# 02_Mobile_Power.net
KiCad netlist of a schematic drawn in Altium Designer
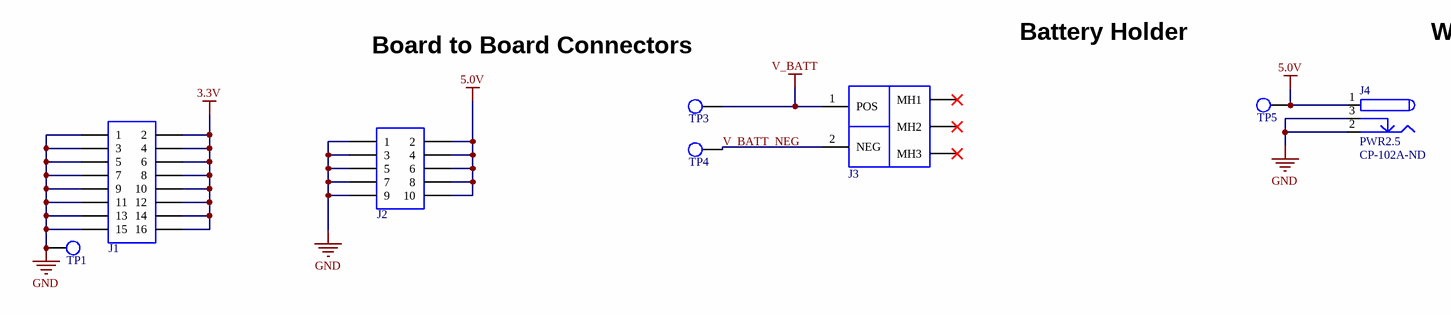
[diagram p0: 02 Mobile Power.SchDoc]

(export (version "E")
  (design (tool "Eeschema 10.0.6"))
  (components
    (comp (ref "J1")
      (value "CONN_HEADER_MALE_8x2")
      (footprint "SBH11-PBPC-D08-ST-BK")
      (description "CONN HEADER 2.54MM 16POS GOLD")
      (fields
        (field (name "MANUFACTURER") "Sullins Connector Solutions")
        (field (name "MANUFACTURER PART NUMBER") "SBH11-PBPC-D08-ST-BK")
      )
      (libsource (lib "ECE453_PWR") (part "CONN_HEADER_MALE_8x2"))
    )
    (comp (ref "J2")
      (value "CONN_HEADER_MALE_5x2")
      (footprint "SBH11-PBPC-D05-ST-BK")
      (description "CONN HEADER 2.54MM 10POS GOLD")
      (fields
        (field (name "MANUFACTURER PART NUMBER") "SBH11-PBPC-D05-ST-BK")
        (field (name "MANUFACTURER") "Sullins Connector Solutions")
      )
      (libsource (lib "ECE453_PWR") (part "CONN_HEADER_MALE_5x2"))
    )
    (comp (ref "J3")
      (value "CONN_BAT_18650")
      (footprint "1043")
      (description "HOLDER FOR 18650 BATTERY")
      (libsource (lib "Battery") (part "CONN_BAT_18650"))
    )
    (comp (ref "J4")
      (value "PWR2.5")
      (footprint "PJ-102")
      (description "Low Voltage Power Supply Connector")
      (fields
        (field (name "MANUFACTURER") "CUI")
        (field (name "MANUFACTURER PART NUMBER") "PJ-102A")
        (field (name "SUPPLIER PART NUMBER 1") "CP-102A-ND")
        (field (name "PUBLISHER") "Altium Limited")
      )
      (libsource (lib "ECE453_PWR") (part "PWR2.5"))
    )
    (comp (ref "TP1")
      (value "TP_1206")
      (footprint "TP-SMC-1206")
      (description "Test Point SMD 1206")
      (libsource (lib "ECE453_PWR") (part "TP_1206"))
    )
    (comp (ref "TP3")
      (value "TP_1206")
      (footprint "TP-SMC-1206")
      (description "Test Point SMD 1206")
      (libsource (lib "ECE453_PWR") (part "TP_1206"))
    )
    (comp (ref "TP4")
      (value "TP_1206")
      (footprint "TP-SMC-1206")
      (description "Test Point SMD 1206")
      (libsource (lib "ECE453_PWR") (part "TP_1206"))
    )
    (comp (ref "TP5")
      (value "TP_1206")
      (footprint "TP-SMC-1206")
      (description "Test Point SMD 1206")
      (libsource (lib "ECE453_PWR") (part "TP_1206"))
    )
  )
  (nets
    (net (code "1") (name "/V_BATT_NEG") (class "Default")
      (node (ref "J3") (pin "2") (pinfunction "NEG_2") (pintype "passive"))
      (node (ref "TP4") (pin "1") (pintype "passive"))
    )
    (net (code "2") (name "3.3V") (class "Default")
      (node (ref "J1") (pin "10") (pinfunction "10_10") (pintype "passive"))
      (node (ref "J1") (pin "12") (pinfunction "12_12") (pintype "passive"))
      (node (ref "J1") (pin "14") (pinfunction "14_14") (pintype "passive"))
      (node (ref "J1") (pin "16") (pinfunction "16_16") (pintype "passive"))
      (node (ref "J1") (pin "2") (pinfunction "2_2") (pintype "passive"))
      (node (ref "J1") (pin "4") (pinfunction "4_4") (pintype "passive"))
      (node (ref "J1") (pin "6") (pinfunction "6_6") (pintype "passive"))
      (node (ref "J1") (pin "8") (pinfunction "8_8") (pintype "passive"))
    )
    (net (code "3") (name "5.0V") (class "Default")
      (node (ref "J2") (pin "10") (pinfunction "10_10") (pintype "passive"))
      (node (ref "J2") (pin "2") (pinfunction "2_2") (pintype "passive"))
      (node (ref "J2") (pin "4") (pinfunction "4_4") (pintype "passive"))
      (node (ref "J2") (pin "6") (pinfunction "6_6") (pintype "passive"))
      (node (ref "J2") (pin "8") (pinfunction "8_8") (pintype "passive"))
      (node (ref "J4") (pin "1") (pinfunction "1_1") (pintype "power_in"))
      (node (ref "TP5") (pin "1") (pintype "passive"))
    )
    (net (code "4") (name "GND") (class "Default")
      (node (ref "J1") (pin "1") (pinfunction "1_1") (pintype "passive"))
      (node (ref "J1") (pin "11") (pinfunction "11_11") (pintype "passive"))
      (node (ref "J1") (pin "13") (pinfunction "13_13") (pintype "passive"))
      (node (ref "J1") (pin "15") (pinfunction "15_15") (pintype "passive"))
      (node (ref "J1") (pin "3") (pinfunction "3_3") (pintype "passive"))
      (node (ref "J1") (pin "5") (pinfunction "5_5") (pintype "passive"))
      (node (ref "J1") (pin "7") (pinfunction "7_7") (pintype "passive"))
      (node (ref "J1") (pin "9") (pinfunction "9_9") (pintype "passive"))
      (node (ref "J2") (pin "1") (pinfunction "1_1") (pintype "passive"))
      (node (ref "J2") (pin "3") (pinfunction "3_3") (pintype "passive"))
      (node (ref "J2") (pin "5") (pinfunction "5_5") (pintype "passive"))
      (node (ref "J2") (pin "7") (pinfunction "7_7") (pintype "passive"))
      (node (ref "J2") (pin "9") (pinfunction "9_9") (pintype "passive"))
      (node (ref "J4") (pin "2") (pinfunction "2_2") (pintype "power_in"))
      (node (ref "J4") (pin "3") (pinfunction "3_3") (pintype "power_in"))
      (node (ref "TP1") (pin "1") (pintype "passive"))
    )
    (net (code "5") (name "V_BATT") (class "Default")
      (node (ref "J3") (pin "1") (pinfunction "POS_1") (pintype "passive"))
      (node (ref "TP3") (pin "1") (pintype "passive"))
    )
    (net (code "6") (name "unconnected-(J3-PadMH1)") (class "Default")
      (node (ref "J3") (pin "MH1") (pinfunction "MH1_MH1") (pintype "passive+no_connect"))
    )
    (net (code "7") (name "unconnected-(J3-PadMH2)") (class "Default")
      (node (ref "J3") (pin "MH2") (pinfunction "MH2_MH2") (pintype "passive+no_connect"))
    )
    (net (code "8") (name "unconnected-(J3-PadMH3)") (class "Default")
      (node (ref "J3") (pin "MH3") (pinfunction "MH3_MH3") (pintype "passive+no_connect"))
    )
  )
)
